# SW_PS_5V.net
KiCad netlist of a schematic drawn in Altium Designer
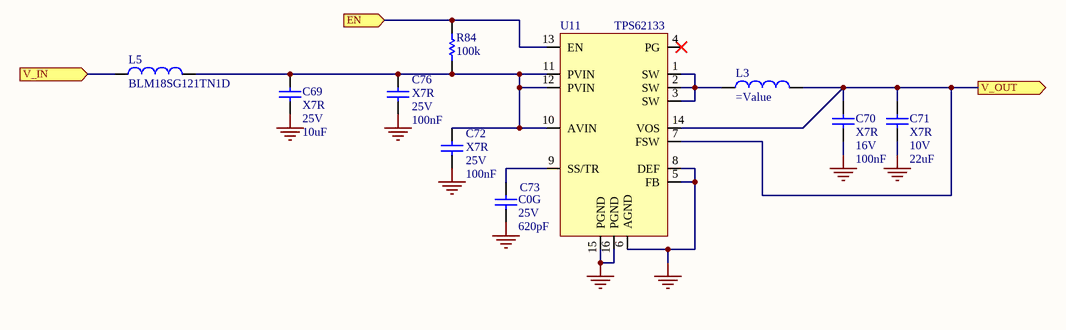
[diagram p0: SW_PS_5V.SchDoc]

(export (version "E")
  (design (tool "Eeschema 10.0.6"))
  (components
    (comp (ref "C69")
      (value "Capacitor")
      (footprint "C1206")
      (description "Capacitor SMD")
      (fields
        (field (name "DIELECTRIC") "X7R")
        (field (name "VOLTAGE") "25V")
        (field (name "CAPACITANCE") "10uF")
        (field (name "PART NUMBER") "C1206_10uF_25V_±10%")
        (field (name "TOLERANCE") "±10%")
      )
      (libsource (lib "Pasives_Capacitor_SMD") (part "Capacitor"))
    )
    (comp (ref "C70")
      (value "Capacitor")
      (footprint "C0603")
      (fields
        (field (name "DIELECTRIC") "X7R")
        (field (name "VOLTAGE") "16V")
        (field (name "CAPACITANCE") "100nF")
        (field (name "PART NUMBER") "C0603_100nF_16V_±10%")
        (field (name "TOLERANCE") "±10%")
        (field (name "MANUFACTURER") "Kemet")
      )
      (libsource (lib "Pasives_Capacitor_SMD") (part "Capacitor"))
    )
    (comp (ref "C71")
      (value "Capacitor")
      (footprint "C1206")
      (fields
        (field (name "DIELECTRIC") "X7R")
        (field (name "VOLTAGE") "10V")
        (field (name "CAPACITANCE") "22uF")
        (field (name "PART NUMBER") "C1206_22uF_10V_±10%")
        (field (name "TOLERANCE") "±10%")
        (field (name "MANUFACTURER") "Taiyo Yuden")
      )
      (libsource (lib "Pasives_Capacitor_SMD") (part "Capacitor"))
    )
    (comp (ref "C72")
      (value "Capacitor")
      (footprint "C0603")
      (fields
        (field (name "DIELECTRIC") "X7R")
        (field (name "VOLTAGE") "25V")
        (field (name "CAPACITANCE") "100nF")
        (field (name "PART NUMBER") "C0603_100nF_25V_±10%")
        (field (name "TOLERANCE") "±10%")
        (field (name "MANUFACTURER") "Kemet")
      )
      (libsource (lib "Pasives_Capacitor_SMD") (part "Capacitor"))
    )
    (comp (ref "C73")
      (value "Capacitor")
      (footprint "C0603")
      (fields
        (field (name "DIELECTRIC") "C0G")
        (field (name "VOLTAGE") "25V")
        (field (name "CAPACITANCE") "620pF")
        (field (name "PART NUMBER") "C0603_620pF_25V_±5%")
        (field (name "TOLERANCE") "±5%")
        (field (name "MANUFACTURER") "Murata")
      )
      (libsource (lib "Pasives_Capacitor_SMD") (part "Capacitor"))
    )
    (comp (ref "C76")
      (value "Capacitor")
      (footprint "C0603")
      (fields
        (field (name "DIELECTRIC") "X7R")
        (field (name "VOLTAGE") "25V")
        (field (name "CAPACITANCE") "100nF")
        (field (name "PART NUMBER") "C0603_100nF_25V_±10%")
        (field (name "TOLERANCE") "±10%")
        (field (name "MANUFACTURER") "Kemet")
      )
      (libsource (lib "Pasives_Capacitor_SMD") (part "Capacitor"))
    )
    (comp (ref "L3")
      (value "~")
      (footprint "TY_NRS6028")
      (fields (field (name "PART NUMBER") "2,2uH_3,7A") (field (name "MANUFACTURER") "Taiyo Yuden"))
      (libsource (lib "Pasivos_Inductor_SMD") (part "Inductor"))
    )
    (comp (ref "L5")
      (value "BLM18SG121TN1D")
      (footprint "L0603")
      (description "Ferrite Bead")
      (fields (field (name "PART NUMBER") "L0603_120R_0,025R_3000mA") (field (name "MANUFACTURER") "Murata"))
      (libsource (lib "Pasivos_Inductor_SMD") (part "Ferrite Bead"))
    )
    (comp (ref "R84")
      (value "100k")
      (footprint "R0603")
      (description "Resistor")
      (fields (field (name "TOLERANCE") "±5%") (field (name "POWER") "0.1W"))
      (libsource (lib "Pasives_Resistor_SMD") (part "Resistor"))
    )
    (comp (ref "U11")
      (value "TPS62133")
      (footprint "QFN16")
      (description "3A High Efficient Synchronous Step Down Converter with DCS™ Control")
      (fields (field (name "MANUFACTURER") "Texas Instruments"))
      (libsource (lib "Power_Regulator") (part "TPS6213x"))
    )
  )
  (nets
    (net (code "1") (name "/EN") (class "Default")
      (node (ref "R84") (pin "2") (pinfunction "2_2") (pintype "passive"))
      (node (ref "U11") (pin "13") (pinfunction "EN_13") (pintype "passive"))
    )
    (net (code "2") (name "/V_IN") (class "Default")
      (node (ref "L5") (pin "1") (pinfunction "1_1") (pintype "passive"))
    )
    (net (code "3") (name "/V_OUT") (class "Default")
      (node (ref "C70") (pin "2") (pinfunction "2_2") (pintype "passive"))
      (node (ref "C71") (pin "2") (pinfunction "2_2") (pintype "passive"))
      (node (ref "L3") (pin "2") (pinfunction "2_2") (pintype "passive"))
      (node (ref "U11") (pin "14") (pinfunction "VOS_14") (pintype "passive"))
      (node (ref "U11") (pin "7") (pinfunction "FSW_7") (pintype "passive"))
    )
    (net (code "4") (name "GND") (class "Default")
      (node (ref "C69") (pin "1") (pinfunction "1_1") (pintype "passive"))
      (node (ref "C70") (pin "1") (pinfunction "1_1") (pintype "passive"))
      (node (ref "C71") (pin "1") (pinfunction "1_1") (pintype "passive"))
      (node (ref "C72") (pin "1") (pinfunction "1_1") (pintype "passive"))
      (node (ref "C73") (pin "1") (pinfunction "1_1") (pintype "passive"))
      (node (ref "C76") (pin "1") (pinfunction "1_1") (pintype "passive"))
      (node (ref "U11") (pin "15") (pinfunction "PGND_15") (pintype "passive"))
      (node (ref "U11") (pin "16") (pinfunction "PGND_16") (pintype "passive"))
      (node (ref "U11") (pin "5") (pinfunction "FB_5") (pintype "passive"))
      (node (ref "U11") (pin "6") (pinfunction "AGND_6") (pintype "passive"))
      (node (ref "U11") (pin "8") (pinfunction "DEF_8") (pintype "passive"))
    )
    (net (code "5") (name "Net-(L3-Pad1)") (class "Default")
      (node (ref "L3") (pin "1") (pinfunction "1_1") (pintype "passive"))
      (node (ref "U11") (pin "1") (pinfunction "SW_1") (pintype "passive"))
      (node (ref "U11") (pin "2") (pinfunction "SW_2") (pintype "passive"))
      (node (ref "U11") (pin "3") (pinfunction "SW_3") (pintype "passive"))
    )
    (net (code "6") (name "Net-(U11-AVIN)") (class "Default")
      (node (ref "C69") (pin "2") (pinfunction "2_2") (pintype "passive"))
      (node (ref "C72") (pin "2") (pinfunction "2_2") (pintype "passive"))
      (node (ref "C76") (pin "2") (pinfunction "2_2") (pintype "passive"))
      (node (ref "L5") (pin "2") (pinfunction "2_2") (pintype "passive"))
      (node (ref "R84") (pin "1") (pinfunction "1_1") (pintype "passive"))
      (node (ref "U11") (pin "10") (pinfunction "AVIN_10") (pintype "passive"))
      (node (ref "U11") (pin "11") (pinfunction "PVIN_11") (pintype "passive"))
      (node (ref "U11") (pin "12") (pinfunction "PVIN_12") (pintype "passive"))
    )
    (net (code "7") (name "Net-(U11-SS{slash}TR)") (class "Default")
      (node (ref "C73") (pin "2") (pinfunction "2_2") (pintype "passive"))
      (node (ref "U11") (pin "9") (pinfunction "SS/TR_9") (pintype "passive"))
    )
    (net (code "8") (name "unconnected-(U11-PG-Pad4)") (class "Default")
      (node (ref "U11") (pin "4") (pinfunction "PG_4") (pintype "passive+no_connect"))
    )
  )
)
